# BOB_O1000.net
KiCad netlist of a schematic drawn in EAGLE
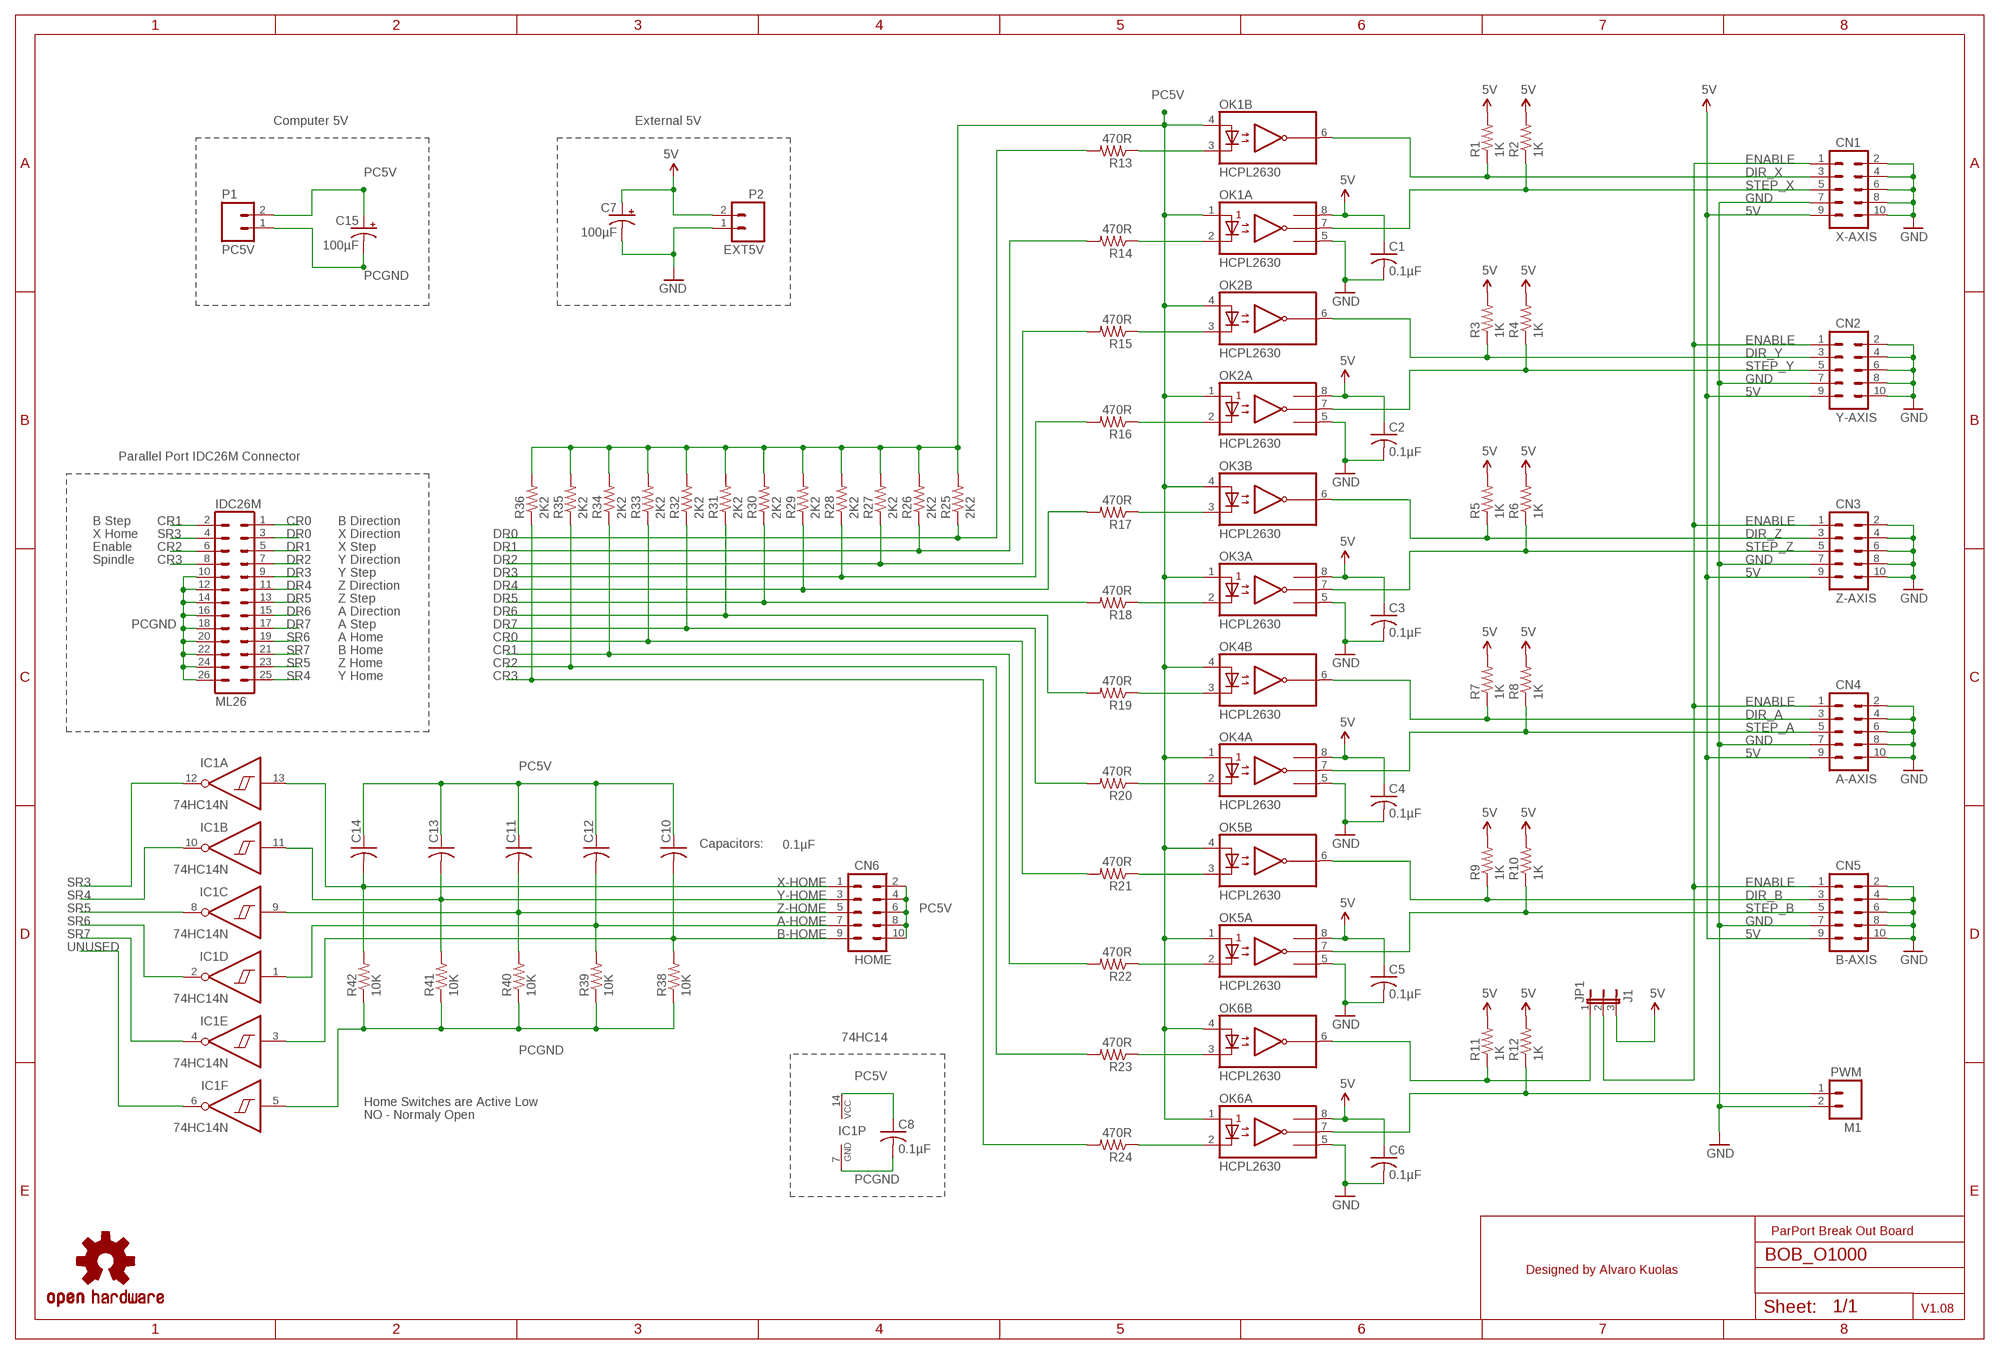
[diagram p0: schematic, sheet 1]

(export (version "E")
  (design (tool "Eeschema 10.0.6"))
  (components
    (comp (ref "C1")
      (value "0.1µF")
      (footprint "eagle-import:C050-024X044")
      (libsource (lib "eagle-import") (part "C-US050-024X044"))
    )
    (comp (ref "C2")
      (value "0.1µF")
      (footprint "eagle-import:C050-024X044")
      (libsource (lib "eagle-import") (part "C-US050-024X044"))
    )
    (comp (ref "C3")
      (value "0.1µF")
      (footprint "eagle-import:C050-024X044")
      (libsource (lib "eagle-import") (part "C-US050-024X044"))
    )
    (comp (ref "C4")
      (value "0.1µF")
      (footprint "eagle-import:C050-024X044")
      (libsource (lib "eagle-import") (part "C-US050-024X044"))
    )
    (comp (ref "C5")
      (value "0.1µF")
      (footprint "eagle-import:C050-024X044")
      (libsource (lib "eagle-import") (part "C-US050-024X044"))
    )
    (comp (ref "C6")
      (value "0.1µF")
      (footprint "eagle-import:C050-024X044")
      (libsource (lib "eagle-import") (part "C-US050-024X044"))
    )
    (comp (ref "C7")
      (value "100µF")
      (footprint "eagle-import:E5-10,5")
      (libsource (lib "eagle-import") (part "CPOL-USE5-10.5"))
    )
    (comp (ref "C8")
      (value "0.1µF")
      (footprint "eagle-import:C050-024X044")
      (libsource (lib "eagle-import") (part "C-US050-024X044"))
    )
    (comp (ref "C10")
      (value "0.1µF")
      (footprint "eagle-import:C050-024X044")
      (libsource (lib "eagle-import") (part "C-US050-024X044"))
    )
    (comp (ref "C11")
      (value "0.1µF")
      (footprint "eagle-import:C050-024X044")
      (libsource (lib "eagle-import") (part "C-US050-024X044"))
    )
    (comp (ref "C12")
      (value "0.1µF")
      (footprint "eagle-import:C050-024X044")
      (libsource (lib "eagle-import") (part "C-US050-024X044"))
    )
    (comp (ref "C13")
      (value "0.1µF")
      (footprint "eagle-import:C050-024X044")
      (libsource (lib "eagle-import") (part "C-US050-024X044"))
    )
    (comp (ref "C14")
      (value "0.1µF")
      (footprint "eagle-import:C050-024X044")
      (libsource (lib "eagle-import") (part "C-US050-024X044"))
    )
    (comp (ref "C15")
      (value "100µF")
      (footprint "eagle-import:E5-10,5")
      (libsource (lib "eagle-import") (part "CPOL-USE5-10.5"))
    )
    (comp (ref "CN1")
      (value "X-AXIS")
      (footprint "eagle-import:2X5-SHROUDED")
      (libsource (lib "eagle-import") (part "M05X2SHD"))
    )
    (comp (ref "CN2")
      (value "Y-AXIS")
      (footprint "eagle-import:2X5-SHROUDED")
      (libsource (lib "eagle-import") (part "M05X2SHD"))
    )
    (comp (ref "CN3")
      (value "Z-AXIS")
      (footprint "eagle-import:2X5-SHROUDED")
      (libsource (lib "eagle-import") (part "M05X2SHD"))
    )
    (comp (ref "CN4")
      (value "A-AXIS")
      (footprint "eagle-import:2X5-SHROUDED")
      (libsource (lib "eagle-import") (part "M05X2SHD"))
    )
    (comp (ref "CN5")
      (value "B-AXIS")
      (footprint "eagle-import:2X5-SHROUDED")
      (libsource (lib "eagle-import") (part "M05X2SHD"))
    )
    (comp (ref "CN6")
      (value "HOME")
      (footprint "eagle-import:2X5-SHROUDED")
      (libsource (lib "eagle-import") (part "M05X2SHD"))
    )
    (comp (ref "IC1")
      (value "74HC14N")
      (footprint "eagle-import:DIL14")
      (libsource (lib "eagle-import") (part "7414NHC"))
    )
    (comp (ref "JP1")
      (value "J1")
      (footprint "eagle-import:1X03")
      (libsource (lib "eagle-import") (part "JUMPER-3PTH"))
    )
    (comp (ref "M1")
      (value "PWM")
      (footprint "eagle-import:1X02")
      (libsource (lib "eagle-import") (part "M02PTH"))
    )
    (comp (ref "ML26")
      (value "IDC26M")
      (footprint "eagle-import:ML26")
      (libsource (lib "eagle-import") (part "ML26"))
    )
    (comp (ref "OK1")
      (value "HCPL2630")
      (footprint "eagle-import:DIL08")
      (libsource (lib "eagle-import") (part "optocoupler-2_HCPL2630"))
    )
    (comp (ref "OK2")
      (value "HCPL2630")
      (footprint "eagle-import:DIL08")
      (libsource (lib "eagle-import") (part "optocoupler-2_HCPL2630"))
    )
    (comp (ref "OK3")
      (value "HCPL2630")
      (footprint "eagle-import:DIL08")
      (libsource (lib "eagle-import") (part "optocoupler-2_HCPL2630"))
    )
    (comp (ref "OK4")
      (value "HCPL2630")
      (footprint "eagle-import:DIL08")
      (libsource (lib "eagle-import") (part "optocoupler-2_HCPL2630"))
    )
    (comp (ref "OK5")
      (value "HCPL2630")
      (footprint "eagle-import:DIL08")
      (libsource (lib "eagle-import") (part "optocoupler-2_HCPL2630"))
    )
    (comp (ref "OK6")
      (value "HCPL2630")
      (footprint "eagle-import:DIL08")
      (libsource (lib "eagle-import") (part "HCPL2630"))
    )
    (comp (ref "P1")
      (value "PC5V")
      (footprint "eagle-import:SCREWTERMINAL-3.5MM-2")
      (libsource (lib "eagle-import") (part "M023.5MM"))
    )
    (comp (ref "P2")
      (value "EXT5V")
      (footprint "eagle-import:SCREWTERMINAL-3.5MM-2")
      (libsource (lib "eagle-import") (part "M023.5MM"))
    )
    (comp (ref "R1")
      (value "1K")
      (footprint "eagle-import:0204_5")
      (libsource (lib "eagle-import") (part "R-US_0204/5"))
    )
    (comp (ref "R2")
      (value "1K")
      (footprint "eagle-import:0204_5")
      (libsource (lib "eagle-import") (part "R-US_0204/5"))
    )
    (comp (ref "R3")
      (value "1K")
      (footprint "eagle-import:0204_5")
      (libsource (lib "eagle-import") (part "R-US_0204/5"))
    )
    (comp (ref "R4")
      (value "1K")
      (footprint "eagle-import:0204_5")
      (libsource (lib "eagle-import") (part "R-US_0204/5"))
    )
    (comp (ref "R5")
      (value "1K")
      (footprint "eagle-import:0204_5")
      (libsource (lib "eagle-import") (part "R-US_0204/5"))
    )
    (comp (ref "R6")
      (value "1K")
      (footprint "eagle-import:0204_5")
      (libsource (lib "eagle-import") (part "R-US_0204/5"))
    )
    (comp (ref "R7")
      (value "1K")
      (footprint "eagle-import:0204_5")
      (libsource (lib "eagle-import") (part "R-US_0204/5"))
    )
    (comp (ref "R8")
      (value "1K")
      (footprint "eagle-import:0204_5")
      (libsource (lib "eagle-import") (part "R-US_0204/5"))
    )
    (comp (ref "R9")
      (value "1K")
      (footprint "eagle-import:0204_5")
      (libsource (lib "eagle-import") (part "R-US_0204/5"))
    )
    (comp (ref "R10")
      (value "1K")
      (footprint "eagle-import:0204_5")
      (libsource (lib "eagle-import") (part "R-US_0204/5"))
    )
    (comp (ref "R11")
      (value "1K")
      (footprint "eagle-import:0204_5")
      (libsource (lib "eagle-import") (part "R-US_0204/5"))
    )
    (comp (ref "R12")
      (value "1K")
      (footprint "eagle-import:0204_5")
      (libsource (lib "eagle-import") (part "R-US_0204/5"))
    )
    (comp (ref "R13")
      (value "470R")
      (footprint "eagle-import:0204_5")
      (libsource (lib "eagle-import") (part "R-US_0204/5"))
    )
    (comp (ref "R14")
      (value "470R")
      (footprint "eagle-import:0204_5")
      (libsource (lib "eagle-import") (part "R-US_0204/5"))
    )
    (comp (ref "R15")
      (value "470R")
      (footprint "eagle-import:0204_5")
      (libsource (lib "eagle-import") (part "R-US_0204/5"))
    )
    (comp (ref "R16")
      (value "470R")
      (footprint "eagle-import:0204_5")
      (libsource (lib "eagle-import") (part "R-US_0204/5"))
    )
    (comp (ref "R17")
      (value "470R")
      (footprint "eagle-import:0204_5")
      (libsource (lib "eagle-import") (part "R-US_0204/5"))
    )
    (comp (ref "R18")
      (value "470R")
      (footprint "eagle-import:0204_5")
      (libsource (lib "eagle-import") (part "R-US_0204/5"))
    )
    (comp (ref "R19")
      (value "470R")
      (footprint "eagle-import:0204_5")
      (libsource (lib "eagle-import") (part "R-US_0204/5"))
    )
    (comp (ref "R20")
      (value "470R")
      (footprint "eagle-import:0204_5")
      (libsource (lib "eagle-import") (part "R-US_0204/5"))
    )
    (comp (ref "R21")
      (value "470R")
      (footprint "eagle-import:0204_5")
      (libsource (lib "eagle-import") (part "R-US_0204/5"))
    )
    (comp (ref "R22")
      (value "470R")
      (footprint "eagle-import:0204_5")
      (libsource (lib "eagle-import") (part "R-US_0204/5"))
    )
    (comp (ref "R23")
      (value "470R")
      (footprint "eagle-import:0204_5")
      (libsource (lib "eagle-import") (part "R-US_0204/5"))
    )
    (comp (ref "R24")
      (value "470R")
      (footprint "eagle-import:0204_5")
      (libsource (lib "eagle-import") (part "R-US_0204/5"))
    )
    (comp (ref "R25")
      (value "2K2")
      (footprint "eagle-import:0204_5")
      (libsource (lib "eagle-import") (part "R-US_0204/5"))
    )
    (comp (ref "R26")
      (value "2K2")
      (footprint "eagle-import:0204_5")
      (libsource (lib "eagle-import") (part "R-US_0204/5"))
    )
    (comp (ref "R27")
      (value "2K2")
      (footprint "eagle-import:0204_5")
      (libsource (lib "eagle-import") (part "R-US_0204/5"))
    )
    (comp (ref "R28")
      (value "2K2")
      (footprint "eagle-import:0204_5")
      (libsource (lib "eagle-import") (part "R-US_0204/5"))
    )
    (comp (ref "R29")
      (value "2K2")
      (footprint "eagle-import:0204_5")
      (libsource (lib "eagle-import") (part "R-US_0204/5"))
    )
    (comp (ref "R30")
      (value "2K2")
      (footprint "eagle-import:0204_5")
      (libsource (lib "eagle-import") (part "R-US_0204/5"))
    )
    (comp (ref "R31")
      (value "2K2")
      (footprint "eagle-import:0204_5")
      (libsource (lib "eagle-import") (part "R-US_0204/5"))
    )
    (comp (ref "R32")
      (value "2K2")
      (footprint "eagle-import:0204_5")
      (libsource (lib "eagle-import") (part "R-US_0204/5"))
    )
    (comp (ref "R33")
      (value "2K2")
      (footprint "eagle-import:0204_5")
      (libsource (lib "eagle-import") (part "R-US_0204/5"))
    )
    (comp (ref "R34")
      (value "2K2")
      (footprint "eagle-import:0204_5")
      (libsource (lib "eagle-import") (part "R-US_0204/5"))
    )
    (comp (ref "R35")
      (value "2K2")
      (footprint "eagle-import:0204_5")
      (libsource (lib "eagle-import") (part "R-US_0204/5"))
    )
    (comp (ref "R36")
      (value "2K2")
      (footprint "eagle-import:0204_5")
      (libsource (lib "eagle-import") (part "R-US_0204/5"))
    )
    (comp (ref "R38")
      (value "10K")
      (footprint "eagle-import:0204_5")
      (libsource (lib "eagle-import") (part "R-US_0204/5"))
    )
    (comp (ref "R39")
      (value "10K")
      (footprint "eagle-import:0204_5")
      (libsource (lib "eagle-import") (part "R-US_0204/5"))
    )
    (comp (ref "R40")
      (value "10K")
      (footprint "eagle-import:0204_5")
      (libsource (lib "eagle-import") (part "R-US_0204/5"))
    )
    (comp (ref "R41")
      (value "10K")
      (footprint "eagle-import:0204_5")
      (libsource (lib "eagle-import") (part "R-US_0204/5"))
    )
    (comp (ref "R42")
      (value "10K")
      (footprint "eagle-import:0204_5")
      (libsource (lib "eagle-import") (part "R-US_0204/5"))
    )
    (comp (ref "U$24")
      (value "OSHW-LOGOL")
      (footprint "eagle-import:OSHW-LOGO-L")
      (libsource (lib "eagle-import") (part "OSHW-LOGOL"))
    )
  )
  (nets
    (net (code "1") (name "/A-HOME") (class "Default")
      (node (ref "C12") (pin "2") (pinfunction "2_2") (pintype "passive"))
      (node (ref "CN6") (pin "7") (pinfunction "7_7") (pintype "passive"))
      (node (ref "IC1") (pin "1") (pinfunction "I_1") (pintype "input"))
      (node (ref "R39") (pin "2") (pinfunction "2_2") (pintype "passive"))
    )
    (net (code "2") (name "/B-HOME") (class "Default")
      (node (ref "C10") (pin "2") (pinfunction "2_2") (pintype "passive"))
      (node (ref "CN6") (pin "9") (pinfunction "9_9") (pintype "passive"))
      (node (ref "IC1") (pin "3") (pinfunction "I_3") (pintype "input"))
      (node (ref "R38") (pin "2") (pinfunction "2_2") (pintype "passive"))
    )
    (net (code "3") (name "/CR0") (class "Default")
      (node (ref "ML26") (pin "1") (pinfunction "1_1") (pintype "passive"))
      (node (ref "R21") (pin "2") (pinfunction "2_2") (pintype "passive"))
      (node (ref "R33") (pin "1") (pinfunction "1_1") (pintype "passive"))
    )
    (net (code "4") (name "/CR1") (class "Default")
      (node (ref "ML26") (pin "2") (pinfunction "2_2") (pintype "passive"))
      (node (ref "R22") (pin "2") (pinfunction "2_2") (pintype "passive"))
      (node (ref "R34") (pin "1") (pinfunction "1_1") (pintype "passive"))
    )
    (net (code "5") (name "/CR2") (class "Default")
      (node (ref "ML26") (pin "6") (pinfunction "6_6") (pintype "passive"))
      (node (ref "R23") (pin "2") (pinfunction "2_2") (pintype "passive"))
      (node (ref "R35") (pin "1") (pinfunction "1_1") (pintype "passive"))
    )
    (net (code "6") (name "/CR3") (class "Default")
      (node (ref "ML26") (pin "8") (pinfunction "8_8") (pintype "passive"))
      (node (ref "R24") (pin "2") (pinfunction "2_2") (pintype "passive"))
      (node (ref "R36") (pin "1") (pinfunction "1_1") (pintype "passive"))
    )
    (net (code "7") (name "/DIR_A") (class "Default")
      (node (ref "CN4") (pin "3") (pinfunction "3_3") (pintype "passive"))
      (node (ref "OK4") (pin "6") (pinfunction "VO2_6") (pintype "passive"))
      (node (ref "R7") (pin "1") (pinfunction "1_1") (pintype "passive"))
    )
    (net (code "8") (name "/DIR_B") (class "Default")
      (node (ref "CN5") (pin "3") (pinfunction "3_3") (pintype "passive"))
      (node (ref "OK5") (pin "6") (pinfunction "VO2_6") (pintype "passive"))
      (node (ref "R9") (pin "1") (pinfunction "1_1") (pintype "passive"))
    )
    (net (code "9") (name "/DIR_X") (class "Default")
      (node (ref "CN1") (pin "3") (pinfunction "3_3") (pintype "passive"))
      (node (ref "OK1") (pin "6") (pinfunction "VO2_6") (pintype "passive"))
      (node (ref "R1") (pin "1") (pinfunction "1_1") (pintype "passive"))
    )
    (net (code "10") (name "/DIR_Y") (class "Default")
      (node (ref "CN2") (pin "3") (pinfunction "3_3") (pintype "passive"))
      (node (ref "OK2") (pin "6") (pinfunction "VO2_6") (pintype "passive"))
      (node (ref "R3") (pin "1") (pinfunction "1_1") (pintype "passive"))
    )
    (net (code "11") (name "/DIR_Z") (class "Default")
      (node (ref "CN3") (pin "3") (pinfunction "3_3") (pintype "passive"))
      (node (ref "OK3") (pin "6") (pinfunction "VO2_6") (pintype "passive"))
      (node (ref "R5") (pin "1") (pinfunction "1_1") (pintype "passive"))
    )
    (net (code "12") (name "/DR0") (class "Default")
      (node (ref "ML26") (pin "3") (pinfunction "3_3") (pintype "passive"))
      (node (ref "R13") (pin "2") (pinfunction "2_2") (pintype "passive"))
      (node (ref "R25") (pin "1") (pinfunction "1_1") (pintype "passive"))
    )
    (net (code "13") (name "/DR1") (class "Default")
      (node (ref "ML26") (pin "5") (pinfunction "5_5") (pintype "passive"))
      (node (ref "R14") (pin "2") (pinfunction "2_2") (pintype "passive"))
      (node (ref "R26") (pin "1") (pinfunction "1_1") (pintype "passive"))
    )
    (net (code "14") (name "/DR2") (class "Default")
      (node (ref "ML26") (pin "7") (pinfunction "7_7") (pintype "passive"))
      (node (ref "R15") (pin "2") (pinfunction "2_2") (pintype "passive"))
      (node (ref "R27") (pin "1") (pinfunction "1_1") (pintype "passive"))
    )
    (net (code "15") (name "/DR3") (class "Default")
      (node (ref "ML26") (pin "9") (pinfunction "9_9") (pintype "passive"))
      (node (ref "R16") (pin "2") (pinfunction "2_2") (pintype "passive"))
      (node (ref "R28") (pin "1") (pinfunction "1_1") (pintype "passive"))
    )
    (net (code "16") (name "/DR4") (class "Default")
      (node (ref "ML26") (pin "11") (pinfunction "11_11") (pintype "passive"))
      (node (ref "R17") (pin "2") (pinfunction "2_2") (pintype "passive"))
      (node (ref "R29") (pin "1") (pinfunction "1_1") (pintype "passive"))
    )
    (net (code "17") (name "/DR5") (class "Default")
      (node (ref "ML26") (pin "13") (pinfunction "13_13") (pintype "passive"))
      (node (ref "R18") (pin "2") (pinfunction "2_2") (pintype "passive"))
      (node (ref "R30") (pin "1") (pinfunction "1_1") (pintype "passive"))
    )
    (net (code "18") (name "/DR6") (class "Default")
      (node (ref "ML26") (pin "15") (pinfunction "15_15") (pintype "passive"))
      (node (ref "R19") (pin "2") (pinfunction "2_2") (pintype "passive"))
      (node (ref "R31") (pin "1") (pinfunction "1_1") (pintype "passive"))
    )
    (net (code "19") (name "/DR7") (class "Default")
      (node (ref "ML26") (pin "17") (pinfunction "17_17") (pintype "passive"))
      (node (ref "R20") (pin "2") (pinfunction "2_2") (pintype "passive"))
      (node (ref "R32") (pin "1") (pinfunction "1_1") (pintype "passive"))
    )
    (net (code "20") (name "/ENABLE") (class "Default")
      (node (ref "CN1") (pin "1") (pinfunction "1_1") (pintype "passive"))
      (node (ref "CN2") (pin "1") (pinfunction "1_1") (pintype "passive"))
      (node (ref "CN3") (pin "1") (pinfunction "1_1") (pintype "passive"))
      (node (ref "CN4") (pin "1") (pinfunction "1_1") (pintype "passive"))
      (node (ref "CN5") (pin "1") (pinfunction "1_1") (pintype "passive"))
      (node (ref "JP1") (pin "2") (pinfunction "2_2") (pintype "passive"))
    )
    (net (code "21") (name "/PC5V") (class "Default")
      (node (ref "C10") (pin "1") (pinfunction "1_1") (pintype "passive"))
      (node (ref "C11") (pin "1") (pinfunction "1_1") (pintype "passive"))
      (node (ref "C12") (pin "1") (pinfunction "1_1") (pintype "passive"))
      (node (ref "C13") (pin "1") (pinfunction "1_1") (pintype "passive"))
      (node (ref "C14") (pin "1") (pinfunction "1_1") (pintype "passive"))
      (node (ref "C15") (pin "+") (pinfunction "+_+") (pintype "passive"))
      (node (ref "C8") (pin "1") (pinfunction "1_1") (pintype "passive"))
      (node (ref "CN6") (pin "10") (pinfunction "10_10") (pintype "passive"))
      (node (ref "CN6") (pin "2") (pinfunction "2_2") (pintype "passive"))
      (node (ref "CN6") (pin "4") (pinfunction "4_4") (pintype "passive"))
      (node (ref "CN6") (pin "6") (pinfunction "6_6") (pintype "passive"))
      (node (ref "CN6") (pin "8") (pinfunction "8_8") (pintype "passive"))
      (node (ref "IC1") (pin "14") (pinfunction "VCC_14") (pintype "power_in"))
      (node (ref "OK1") (pin "1") (pinfunction "A1_1") (pintype "passive"))
      (node (ref "OK1") (pin "4") (pinfunction "A2_4") (pintype "passive"))
      (node (ref "OK2") (pin "1") (pinfunction "A1_1") (pintype "passive"))
      (node (ref "OK2") (pin "4") (pinfunction "A2_4") (pintype "passive"))
      (node (ref "OK3") (pin "1") (pinfunction "A1_1") (pintype "passive"))
      (node (ref "OK3") (pin "4") (pinfunction "A2_4") (pintype "passive"))
      (node (ref "OK4") (pin "1") (pinfunction "A1_1") (pintype "passive"))
      (node (ref "OK4") (pin "4") (pinfunction "A2_4") (pintype "passive"))
      (node (ref "OK5") (pin "1") (pinfunction "A1_1") (pintype "passive"))
      (node (ref "OK5") (pin "4") (pinfunction "A2_4") (pintype "passive"))
      (node (ref "OK6") (pin "1") (pinfunction "A1_1") (pintype "passive"))
      (node (ref "OK6") (pin "4") (pinfunction "A2_4") (pintype "passive"))
      (node (ref "P1") (pin "2") (pinfunction "2_2") (pintype "passive"))
      (node (ref "R25") (pin "2") (pinfunction "2_2") (pintype "passive"))
      (node (ref "R26") (pin "2") (pinfunction "2_2") (pintype "passive"))
      (node (ref "R27") (pin "2") (pinfunction "2_2") (pintype "passive"))
      (node (ref "R28") (pin "2") (pinfunction "2_2") (pintype "passive"))
      (node (ref "R29") (pin "2") (pinfunction "2_2") (pintype "passive"))
      (node (ref "R30") (pin "2") (pinfunction "2_2") (pintype "passive"))
      (node (ref "R31") (pin "2") (pinfunction "2_2") (pintype "passive"))
      (node (ref "R32") (pin "2") (pinfunction "2_2") (pintype "passive"))
      (node (ref "R33") (pin "2") (pinfunction "2_2") (pintype "passive"))
      (node (ref "R34") (pin "2") (pinfunction "2_2") (pintype "passive"))
      (node (ref "R35") (pin "2") (pinfunction "2_2") (pintype "passive"))
      (node (ref "R36") (pin "2") (pinfunction "2_2") (pintype "passive"))
    )
    (net (code "22") (name "/PCGND") (class "Default")
      (node (ref "C15") (pin "-") (pinfunction "-_-") (pintype "passive"))
      (node (ref "C8") (pin "2") (pinfunction "2_2") (pintype "passive"))
      (node (ref "IC1") (pin "5") (pinfunction "I_5") (pintype "input"))
      (node (ref "IC1") (pin "7") (pinfunction "GND_7") (pintype "power_in"))
      (node (ref "ML26") (pin "10") (pinfunction "10_10") (pintype "passive"))
      (node (ref "ML26") (pin "12") (pinfunction "12_12") (pintype "passive"))
      (node (ref "ML26") (pin "14") (pinfunction "14_14") (pintype "passive"))
      (node (ref "ML26") (pin "16") (pinfunction "16_16") (pintype "passive"))
      (node (ref "ML26") (pin "18") (pinfunction "18_18") (pintype "passive"))
      (node (ref "ML26") (pin "20") (pinfunction "20_20") (pintype "passive"))
      (node (ref "ML26") (pin "22") (pinfunction "22_22") (pintype "passive"))
      (node (ref "ML26") (pin "24") (pinfunction "24_24") (pintype "passive"))
      (node (ref "ML26") (pin "26") (pinfunction "26_26") (pintype "passive"))
      (node (ref "P1") (pin "1") (pinfunction "1_1") (pintype "passive"))
      (node (ref "R38") (pin "1") (pinfunction "1_1") (pintype "passive"))
      (node (ref "R39") (pin "1") (pinfunction "1_1") (pintype "passive"))
      (node (ref "R40") (pin "1") (pinfunction "1_1") (pintype "passive"))
      (node (ref "R41") (pin "1") (pinfunction "1_1") (pintype "passive"))
      (node (ref "R42") (pin "1") (pinfunction "1_1") (pintype "passive"))
    )
    (net (code "23") (name "/SR3") (class "Default")
      (node (ref "IC1") (pin "12") (pinfunction "O_12") (pintype "output"))
      (node (ref "ML26") (pin "4") (pinfunction "4_4") (pintype "passive"))
    )
    (net (code "24") (name "/SR4") (class "Default")
      (node (ref "IC1") (pin "10") (pinfunction "O_10") (pintype "output"))
      (node (ref "ML26") (pin "25") (pinfunction "25_25") (pintype "passive"))
    )
    (net (code "25") (name "/SR5") (class "Default")
      (node (ref "IC1") (pin "8") (pinfunction "O_8") (pintype "output"))
      (node (ref "ML26") (pin "23") (pinfunction "23_23") (pintype "passive"))
    )
    (net (code "26") (name "/SR6") (class "Default")
      (node (ref "IC1") (pin "2") (pinfunction "O_2") (pintype "output"))
      (node (ref "ML26") (pin "19") (pinfunction "19_19") (pintype "passive"))
    )
    (net (code "27") (name "/SR7") (class "Default")
      (node (ref "IC1") (pin "4") (pinfunction "O_4") (pintype "output"))
      (node (ref "ML26") (pin "21") (pinfunction "21_21") (pintype "passive"))
    )
    (net (code "28") (name "/STEP_A") (class "Default")
      (node (ref "CN4") (pin "5") (pinfunction "5_5") (pintype "passive"))
      (node (ref "OK4") (pin "7") (pinfunction "VO1_7") (pintype "passive"))
      (node (ref "R8") (pin "1") (pinfunction "1_1") (pintype "passive"))
    )
    (net (code "29") (name "/STEP_B") (class "Default")
      (node (ref "CN5") (pin "5") (pinfunction "5_5") (pintype "passive"))
      (node (ref "OK5") (pin "7") (pinfunction "VO1_7") (pintype "passive"))
      (node (ref "R10") (pin "1") (pinfunction "1_1") (pintype "passive"))
    )
    (net (code "30") (name "/STEP_X") (class "Default")
      (node (ref "CN1") (pin "5") (pinfunction "5_5") (pintype "passive"))
      (node (ref "OK1") (pin "7") (pinfunction "VO1_7") (pintype "passive"))
      (node (ref "R2") (pin "1") (pinfunction "1_1") (pintype "passive"))
    )
    (net (code "31") (name "/STEP_Y") (class "Default")
      (node (ref "CN2") (pin "5") (pinfunction "5_5") (pintype "passive"))
      (node (ref "OK2") (pin "7") (pinfunction "VO1_7") (pintype "passive"))
      (node (ref "R4") (pin "1") (pinfunction "1_1") (pintype "passive"))
    )
    (net (code "32") (name "/STEP_Z") (class "Default")
      (node (ref "CN3") (pin "5") (pinfunction "5_5") (pintype "passive"))
      (node (ref "OK3") (pin "7") (pinfunction "VO1_7") (pintype "passive"))
      (node (ref "R6") (pin "1") (pinfunction "1_1") (pintype "passive"))
    )
    (net (code "33") (name "/UNUSED") (class "Default")
      (node (ref "IC1") (pin "6") (pinfunction "O_6") (pintype "output"))
    )
    (net (code "34") (name "/X-HOME") (class "Default")
      (node (ref "C14") (pin "2") (pinfunction "2_2") (pintype "passive"))
      (node (ref "CN6") (pin "1") (pinfunction "1_1") (pintype "passive"))
      (node (ref "IC1") (pin "13") (pinfunction "I_13") (pintype "input"))
      (node (ref "R42") (pin "2") (pinfunction "2_2") (pintype "passive"))
    )
    (net (code "35") (name "/Y-HOME") (class "Default")
      (node (ref "C13") (pin "2") (pinfunction "2_2") (pintype "passive"))
      (node (ref "CN6") (pin "3") (pinfunction "3_3") (pintype "passive"))
      (node (ref "IC1") (pin "11") (pinfunction "I_11") (pintype "input"))
      (node (ref "R41") (pin "2") (pinfunction "2_2") (pintype "passive"))
    )
    (net (code "36") (name "/Z-HOME") (class "Default")
      (node (ref "C11") (pin "2") (pinfunction "2_2") (pintype "passive"))
      (node (ref "CN6") (pin "5") (pinfunction "5_5") (pintype "passive"))
      (node (ref "IC1") (pin "9") (pinfunction "I_9") (pintype "input"))
      (node (ref "R40") (pin "2") (pinfunction "2_2") (pintype "passive"))
    )
    (net (code "37") (name "5V") (class "Default")
      (node (ref "C1") (pin "1") (pinfunction "1_1") (pintype "passive"))
      (node (ref "C2") (pin "1") (pinfunction "1_1") (pintype "passive"))
      (node (ref "C3") (pin "1") (pinfunction "1_1") (pintype "passive"))
      (node (ref "C4") (pin "1") (pinfunction "1_1") (pintype "passive"))
      (node (ref "C5") (pin "1") (pinfunction "1_1") (pintype "passive"))
      (node (ref "C6") (pin "1") (pinfunction "1_1") (pintype "passive"))
      (node (ref "C7") (pin "+") (pinfunction "+_+") (pintype "passive"))
      (node (ref "CN1") (pin "9") (pinfunction "9_9") (pintype "passive"))
      (node (ref "CN2") (pin "9") (pinfunction "9_9") (pintype "passive"))
      (node (ref "CN3") (pin "9") (pinfunction "9_9") (pintype "passive"))
      (node (ref "CN4") (pin "9") (pinfunction "9_9") (pintype "passive"))
      (node (ref "CN5") (pin "9") (pinfunction "9_9") (pintype "passive"))
      (node (ref "JP1") (pin "3") (pinfunction "3_3") (pintype "passive"))
      (node (ref "OK1") (pin "8") (pinfunction "VCC_8") (pintype "passive"))
      (node (ref "OK2") (pin "8") (pinfunction "VCC_8") (pintype "passive"))
      (node (ref "OK3") (pin "8") (pinfunction "VCC_8") (pintype "passive"))
      (node (ref "OK4") (pin "8") (pinfunction "VCC_8") (pintype "passive"))
      (node (ref "OK5") (pin "8") (pinfunction "VCC_8") (pintype "passive"))
      (node (ref "OK6") (pin "8") (pinfunction "VCC_8") (pintype "passive"))
      (node (ref "P2") (pin "2") (pinfunction "2_2") (pintype "passive"))
      (node (ref "R1") (pin "2") (pinfunction "2_2") (pintype "passive"))
      (node (ref "R10") (pin "2") (pinfunction "2_2") (pintype "passive"))
      (node (ref "R11") (pin "2") (pinfunction "2_2") (pintype "passive"))
      (node (ref "R12") (pin "2") (pinfunction "2_2") (pintype "passive"))
      (node (ref "R2") (pin "2") (pinfunction "2_2") (pintype "passive"))
      (node (ref "R3") (pin "2") (pinfunction "2_2") (pintype "passive"))
      (node (ref "R4") (pin "2") (pinfunction "2_2") (pintype "passive"))
      (node (ref "R5") (pin "2") (pinfunction "2_2") (pintype "passive"))
      (node (ref "R6") (pin "2") (pinfunction "2_2") (pintype "passive"))
      (node (ref "R7") (pin "2") (pinfunction "2_2") (pintype "passive"))
      (node (ref "R8") (pin "2") (pinfunction "2_2") (pintype "passive"))
      (node (ref "R9") (pin "2") (pinfunction "2_2") (pintype "passive"))
    )
    (net (code "38") (name "GND") (class "Default")
      (node (ref "C1") (pin "2") (pinfunction "2_2") (pintype "passive"))
      (node (ref "C2") (pin "2") (pinfunction "2_2") (pintype "passive"))
      (node (ref "C3") (pin "2") (pinfunction "2_2") (pintype "passive"))
      (node (ref "C4") (pin "2") (pinfunction "2_2") (pintype "passive"))
      (node (ref "C5") (pin "2") (pinfunction "2_2") (pintype "passive"))
      (node (ref "C6") (pin "2") (pinfunction "2_2") (pintype "passive"))
      (node (ref "C7") (pin "-") (pinfunction "-_-") (pintype "passive"))
      (node (ref "CN1") (pin "10") (pinfunction "10_10") (pintype "passive"))
      (node (ref "CN1") (pin "2") (pinfunction "2_2") (pintype "passive"))
      (node (ref "CN1") (pin "4") (pinfunction "4_4") (pintype "passive"))
      (node (ref "CN1") (pin "6") (pinfunction "6_6") (pintype "passive"))
      (node (ref "CN1") (pin "7") (pinfunction "7_7") (pintype "passive"))
      (node (ref "CN1") (pin "8") (pinfunction "8_8") (pintype "passive"))
      (node (ref "CN2") (pin "10") (pinfunction "10_10") (pintype "passive"))
      (node (ref "CN2") (pin "2") (pinfunction "2_2") (pintype "passive"))
      (node (ref "CN2") (pin "4") (pinfunction "4_4") (pintype "passive"))
      (node (ref "CN2") (pin "6") (pinfunction "6_6") (pintype "passive"))
      (node (ref "CN2") (pin "7") (pinfunction "7_7") (pintype "passive"))
      (node (ref "CN2") (pin "8") (pinfunction "8_8") (pintype "passive"))
      (node (ref "CN3") (pin "10") (pinfunction "10_10") (pintype "passive"))
      (node (ref "CN3") (pin "2") (pinfunction "2_2") (pintype "passive"))
      (node (ref "CN3") (pin "4") (pinfunction "4_4") (pintype "passive"))
      (node (ref "CN3") (pin "6") (pinfunction "6_6") (pintype "passive"))
      (node (ref "CN3") (pin "7") (pinfunction "7_7") (pintype "passive"))
      (node (ref "CN3") (pin "8") (pinfunction "8_8") (pintype "passive"))
      (node (ref "CN4") (pin "10") (pinfunction "10_10") (pintype "passive"))
      (node (ref "CN4") (pin "2") (pinfunction "2_2") (pintype "passive"))
      (node (ref "CN4") (pin "4") (pinfunction "4_4") (pintype "passive"))
      (node (ref "CN4") (pin "6") (pinfunction "6_6") (pintype "passive"))
      (node (ref "CN4") (pin "7") (pinfunction "7_7") (pintype "passive"))
      (node (ref "CN4") (pin "8") (pinfunction "8_8") (pintype "passive"))
      (node (ref "CN5") (pin "10") (pinfunction "10_10") (pintype "passive"))
      (node (ref "CN5") (pin "2") (pinfunction "2_2") (pintype "passive"))
      (node (ref "CN5") (pin "4") (pinfunction "4_4") (pintype "passive"))
      (node (ref "CN5") (pin "6") (pinfunction "6_6") (pintype "passive"))
      (node (ref "CN5") (pin "7") (pinfunction "7_7") (pintype "passive"))
      (node (ref "CN5") (pin "8") (pinfunction "8_8") (pintype "passive"))
      (node (ref "M1") (pin "2") (pinfunction "2_2") (pintype "passive"))
      (node (ref "OK1") (pin "5") (pinfunction "GND_5") (pintype "passive"))
      (node (ref "OK2") (pin "5") (pinfunction "GND_5") (pintype "passive"))
      (node (ref "OK3") (pin "5") (pinfunction "GND_5") (pintype "passive"))
      (node (ref "OK4") (pin "5") (pinfunction "GND_5") (pintype "passive"))
      (node (ref "OK5") (pin "5") (pinfunction "GND_5") (pintype "passive"))
      (node (ref "OK6") (pin "5") (pinfunction "GND_5") (pintype "passive"))
      (node (ref "P2") (pin "1") (pinfunction "1_1") (pintype "passive"))
    )
    (net (code "39") (name "Net-(OK1A-C1)") (class "Default")
      (node (ref "OK1") (pin "2") (pinfunction "C1_2") (pintype "passive"))
      (node (ref "R14") (pin "1") (pinfunction "1_1") (pintype "passive"))
    )
    (net (code "40") (name "Net-(OK1B-C2)") (class "Default")
      (node (ref "OK1") (pin "3") (pinfunction "C2_3") (pintype "passive"))
      (node (ref "R13") (pin "1") (pinfunction "1_1") (pintype "passive"))
    )
    (net (code "41") (name "Net-(OK2A-C1)") (class "Default")
      (node (ref "OK2") (pin "2") (pinfunction "C1_2") (pintype "passive"))
      (node (ref "R16") (pin "1") (pinfunction "1_1") (pintype "passive"))
    )
    (net (code "42") (name "Net-(OK2B-C2)") (class "Default")
      (node (ref "OK2") (pin "3") (pinfunction "C2_3") (pintype "passive"))
      (node (ref "R15") (pin "1") (pinfunction "1_1") (pintype "passive"))
    )
    (net (code "43") (name "Net-(OK3A-C1)") (class "Default")
      (node (ref "OK3") (pin "2") (pinfunction "C1_2") (pintype "passive"))
      (node (ref "R18") (pin "1") (pinfunction "1_1") (pintype "passive"))
    )
    (net (code "44") (name "Net-(OK3B-C2)") (class "Default")
      (node (ref "OK3") (pin "3") (pinfunction "C2_3") (pintype "passive"))
      (node (ref "R17") (pin "1") (pinfunction "1_1") (pintype "passive"))
    )
    (net (code "45") (name "Net-(OK4A-C1)") (class "Default")
      (node (ref "OK4") (pin "2") (pinfunction "C1_2") (pintype "passive"))
      (node (ref "R20") (pin "1") (pinfunction "1_1") (pintype "passive"))
    )
    (net (code "46") (name "Net-(OK4B-C2)") (class "Default")
      (node (ref "OK4") (pin "3") (pinfunction "C2_3") (pintype "passive"))
      (node (ref "R19") (pin "1") (pinfunction "1_1") (pintype "passive"))
    )
    (net (code "47") (name "Net-(OK5A-C1)") (class "Default")
      (node (ref "OK5") (pin "2") (pinfunction "C1_2") (pintype "passive"))
      (node (ref "R22") (pin "1") (pinfunction "1_1") (pintype "passive"))
    )
    (net (code "48") (name "Net-(OK5B-C2)") (class "Default")
      (node (ref "OK5") (pin "3") (pinfunction "C2_3") (pintype "passive"))
      (node (ref "R21") (pin "1") (pinfunction "1_1") (pintype "passive"))
    )
    (net (code "49") (name "Net-(OK6A-C1)") (class "Default")
      (node (ref "OK6") (pin "2") (pinfunction "C1_2") (pintype "passive"))
      (node (ref "R24") (pin "1") (pinfunction "1_1") (pintype "passive"))
    )
    (net (code "50") (name "Net-(OK6A-VO1)") (class "Default")
      (node (ref "M1") (pin "1") (pinfunction "1_1") (pintype "passive"))
      (node (ref "OK6") (pin "7") (pinfunction "VO1_7") (pintype "passive"))
      (node (ref "R12") (pin "1") (pinfunction "1_1") (pintype "passive"))
    )
    (net (code "51") (name "Net-(OK6B-C2)") (class "Default")
      (node (ref "OK6") (pin "3") (pinfunction "C2_3") (pintype "passive"))
      (node (ref "R23") (pin "1") (pinfunction "1_1") (pintype "passive"))
    )
    (net (code "52") (name "Net-(OK6B-VO2)") (class "Default")
      (node (ref "JP1") (pin "1") (pinfunction "1_1") (pintype "passive"))
      (node (ref "OK6") (pin "6") (pinfunction "VO2_6") (pintype "passive"))
      (node (ref "R11") (pin "1") (pinfunction "1_1") (pintype "passive"))
    )
  )
)
